# AUX_POWER.net
KiCad netlist of a schematic drawn in Altium Designer
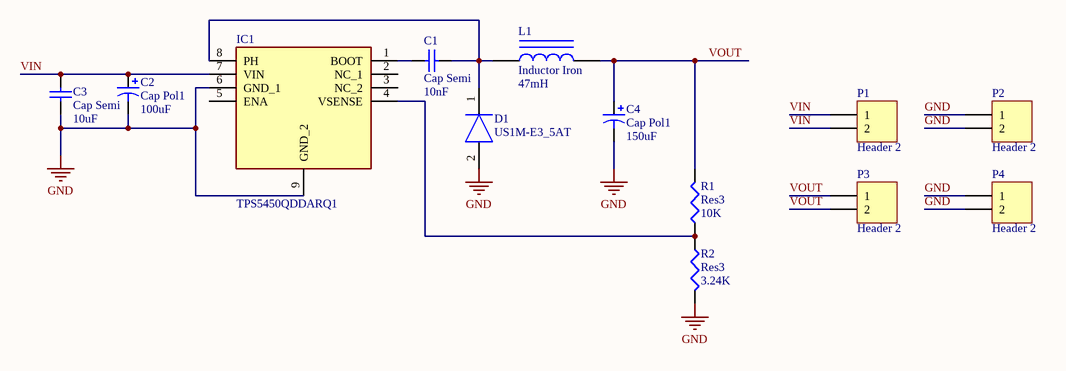
[diagram p0: AUX_POWER.SchDoc]

(export (version "E")
  (design (tool "Eeschema 10.0.6"))
  (components
    (comp (ref "C1")
      (value "Cap Semi")
      (footprint "1608[0603]")
      (description "Capacitor (Semiconductor SIM Model)")
      (fields (field (name "ALTIUM_VALUE") "10nF") (field (name "PUBLISHER") "Altium Limited"))
      (libsource (lib "Miscellaneous Devices") (part "Cap Semi"))
    )
    (comp (ref "C2")
      (value "Cap Pol1")
      (footprint "CAP-8*10.5")
      (description "Polarized Capacitor (Radial)")
      (fields (field (name "ALTIUM_VALUE") "100uF") (field (name "PUBLISHER") "Altium Limited"))
      (libsource (lib "Miscellaneous Devices") (part "Cap Pol1"))
    )
    (comp (ref "C3")
      (value "Cap Semi")
      (footprint "C1206")
      (description "Capacitor (Semiconductor SIM Model)")
      (fields (field (name "ALTIUM_VALUE") "10uF") (field (name "PUBLISHER") "Altium Limited"))
      (libsource (lib "Miscellaneous Devices") (part "Cap Semi"))
    )
    (comp (ref "C4")
      (value "Cap Pol1")
      (footprint "CAP-8*10.5")
      (description "Polarized Capacitor (Radial)")
      (fields (field (name "ALTIUM_VALUE") "150uF") (field (name "PUBLISHER") "Altium Limited"))
      (libsource (lib "Miscellaneous Devices") (part "Cap Pol1"))
    )
    (comp (ref "D1")
      (value "US1M-E3_5AT")
      (footprint "SamacSys:DIOM5127X229N")
      (description "Diode")
      (fields
        (field (name "MANUFACTURER_PART_NUMBER") "US1M-E3/5AT")
        (field (name "MOUSER PART NUMBER") "625-US1M-E3/5AT")
      )
      (libsource (lib "*") (part "US1M-E3_5AT"))
    )
    (comp (ref "IC1")
      (value "TPS5450QDDARQ1")
      (footprint "SamacSys:SOIC127P600X170-9N")
      (description "Integrated Circuit")
      (fields (field (name "MOUSER PART NUMBER") "595-TPS5450QDDARQ1"))
      (libsource (lib "*") (part "TPS5450QDDARQ1"))
    )
    (comp (ref "L1")
      (value "Inductor Iron")
      (footprint "CDRH127")
      (description "Magnetic-Core Inductor")
      (fields (field (name "ALTIUM_VALUE") "47mH") (field (name "PUBLISHER") "Altium Limited"))
      (libsource (lib "Miscellaneous Devices") (part "Inductor Iron"))
    )
    (comp (ref "P1")
      (value "Header 2")
      (footprint "HDR1X2")
      (description "Header, 2-Pin")
      (fields (field (name "PUBLISHER") "Altium Limited"))
      (libsource (lib "Miscellaneous Connectors") (part "Header 2"))
    )
    (comp (ref "P2")
      (value "Header 2")
      (footprint "HDR1X2")
      (description "Header, 2-Pin")
      (fields (field (name "PUBLISHER") "Altium Limited"))
      (libsource (lib "Miscellaneous Connectors") (part "Header 2"))
    )
    (comp (ref "P3")
      (value "Header 2")
      (footprint "HDR1X2")
      (description "Header, 2-Pin")
      (fields (field (name "PUBLISHER") "Altium Limited"))
      (libsource (lib "Miscellaneous Connectors") (part "Header 2"))
    )
    (comp (ref "P4")
      (value "Header 2")
      (footprint "HDR1X2")
      (description "Header, 2-Pin")
      (fields (field (name "PUBLISHER") "Altium Limited"))
      (libsource (lib "Miscellaneous Connectors") (part "Header 2"))
    )
    (comp (ref "R1")
      (value "Res3")
      (footprint "J1-0603")
      (description "Resistor")
      (fields (field (name "ALTIUM_VALUE") "10K") (field (name "PUBLISHER") "Altium Limited"))
      (libsource (lib "Miscellaneous Devices") (part "Res3"))
    )
    (comp (ref "R2")
      (value "Res3")
      (footprint "J1-0603")
      (description "Resistor")
      (fields (field (name "ALTIUM_VALUE") "3.24K") (field (name "PUBLISHER") "Altium Limited"))
      (libsource (lib "Miscellaneous Devices") (part "Res3"))
    )
  )
  (nets
    (net (code "1") (name "/VIN") (class "Default")
      (node (ref "C2") (pin "1") (pinfunction "1_1") (pintype "passive"))
      (node (ref "C3") (pin "2") (pinfunction "2_2") (pintype "passive"))
      (node (ref "IC1") (pin "7") (pinfunction "VIN_7") (pintype "passive"))
      (node (ref "P1") (pin "1") (pinfunction "1_1") (pintype "passive"))
      (node (ref "P1") (pin "2") (pinfunction "2_2") (pintype "passive"))
    )
    (net (code "2") (name "/VOUT") (class "Default")
      (node (ref "C4") (pin "1") (pinfunction "1_1") (pintype "passive"))
      (node (ref "L1") (pin "2") (pinfunction "2_2") (pintype "passive"))
      (node (ref "P3") (pin "1") (pinfunction "1_1") (pintype "passive"))
      (node (ref "P3") (pin "2") (pinfunction "2_2") (pintype "passive"))
      (node (ref "R1") (pin "2") (pinfunction "2_2") (pintype "passive"))
    )
    (net (code "3") (name "GND") (class "Default")
      (node (ref "C2") (pin "2") (pinfunction "2_2") (pintype "passive"))
      (node (ref "C3") (pin "1") (pinfunction "1_1") (pintype "passive"))
      (node (ref "C4") (pin "2") (pinfunction "2_2") (pintype "passive"))
      (node (ref "D1") (pin "2") (pinfunction "A_2") (pintype "passive"))
      (node (ref "IC1") (pin "6") (pinfunction "GND_1_6") (pintype "passive"))
      (node (ref "IC1") (pin "9") (pinfunction "GND_2_9") (pintype "passive"))
      (node (ref "P2") (pin "1") (pinfunction "1_1") (pintype "passive"))
      (node (ref "P2") (pin "2") (pinfunction "2_2") (pintype "passive"))
      (node (ref "P4") (pin "1") (pinfunction "1_1") (pintype "passive"))
      (node (ref "P4") (pin "2") (pinfunction "2_2") (pintype "passive"))
      (node (ref "R2") (pin "2") (pinfunction "2_2") (pintype "passive"))
    )
    (net (code "4") (name "Net-(D1-K)") (class "Default")
      (node (ref "C1") (pin "2") (pinfunction "2_2") (pintype "passive"))
      (node (ref "D1") (pin "1") (pinfunction "K_1") (pintype "passive"))
      (node (ref "IC1") (pin "8") (pinfunction "PH_8") (pintype "passive"))
      (node (ref "L1") (pin "1") (pinfunction "1_1") (pintype "passive"))
    )
    (net (code "5") (name "Net-(IC1-BOOT)") (class "Default")
      (node (ref "C1") (pin "1") (pinfunction "1_1") (pintype "passive"))
      (node (ref "IC1") (pin "1") (pinfunction "BOOT_1") (pintype "passive"))
    )
    (net (code "6") (name "Net-(IC1-VSENSE)") (class "Default")
      (node (ref "IC1") (pin "4") (pinfunction "VSENSE_4") (pintype "passive"))
      (node (ref "R1") (pin "1") (pinfunction "1_1") (pintype "passive"))
      (node (ref "R2") (pin "1") (pinfunction "1_1") (pintype "passive"))
    )
    (net (code "7") (name "unconnected-(IC1-ENA-Pad5)") (class "Default")
      (node (ref "IC1") (pin "5") (pinfunction "ENA_5") (pintype "passive"))
    )
    (net (code "8") (name "unconnected-(IC1-NC_1-Pad2)") (class "Default")
      (node (ref "IC1") (pin "2") (pinfunction "NC_1_2") (pintype "passive"))
    )
    (net (code "9") (name "unconnected-(IC1-NC_2-Pad3)") (class "Default")
      (node (ref "IC1") (pin "3") (pinfunction "NC_2_3") (pintype "passive"))
    )
  )
)
